# SOP-8_2_PCB.net
KiCad netlist of a schematic drawn in EAGLE
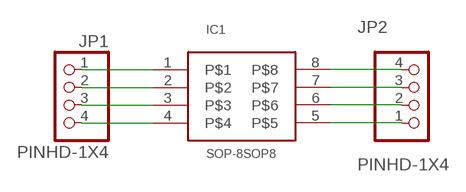
[diagram p0: schematic, sheet 1]

(export (version "E")
  (design (tool "Eeschema 10.0.6"))
  (components
    (comp (ref "IC1")
      (value "SOP-8SOP8")
      (footprint "eagle-import:SOP-8")
      (fields (field (name "MF") "Microchip") (field (name "MP") "AT24C02"))
      (libsource (lib "eagle-import") (part "SOP-8SOP8"))
    )
    (comp (ref "JP1")
      (value "PINHD-1X4")
      (footprint "eagle-import:1X04")
      (libsource (lib "eagle-import") (part "PINHD-1X4"))
    )
    (comp (ref "JP2")
      (value "PINHD-1X4")
      (footprint "eagle-import:1X04")
      (libsource (lib "eagle-import") (part "PINHD-1X4"))
    )
  )
  (nets
    (net (code "1") (name "Net-(IC1-P$1)") (class "Default")
      (node (ref "IC1") (pin "1") (pinfunction "P$1_1") (pintype "bidirectional"))
      (node (ref "JP1") (pin "1") (pinfunction "1_1") (pintype "passive"))
    )
    (net (code "2") (name "Net-(IC1-P$2)") (class "Default")
      (node (ref "IC1") (pin "2") (pinfunction "P$2_2") (pintype "bidirectional"))
      (node (ref "JP1") (pin "2") (pinfunction "2_2") (pintype "passive"))
    )
    (net (code "3") (name "Net-(IC1-P$3)") (class "Default")
      (node (ref "IC1") (pin "3") (pinfunction "P$3_3") (pintype "bidirectional"))
      (node (ref "JP1") (pin "3") (pinfunction "3_3") (pintype "passive"))
    )
    (net (code "4") (name "Net-(IC1-P$4)") (class "Default")
      (node (ref "IC1") (pin "4") (pinfunction "P$4_4") (pintype "bidirectional"))
      (node (ref "JP1") (pin "4") (pinfunction "4_4") (pintype "passive"))
    )
    (net (code "5") (name "Net-(IC1-P$5)") (class "Default")
      (node (ref "IC1") (pin "5") (pinfunction "P$5_5") (pintype "bidirectional"))
      (node (ref "JP2") (pin "1") (pinfunction "1_1") (pintype "passive"))
    )
    (net (code "6") (name "Net-(IC1-P$6)") (class "Default")
      (node (ref "IC1") (pin "6") (pinfunction "P$6_6") (pintype "bidirectional"))
      (node (ref "JP2") (pin "2") (pinfunction "2_2") (pintype "passive"))
    )
    (net (code "7") (name "Net-(IC1-P$7)") (class "Default")
      (node (ref "IC1") (pin "7") (pinfunction "P$7_7") (pintype "bidirectional"))
      (node (ref "JP2") (pin "3") (pinfunction "3_3") (pintype "passive"))
    )
    (net (code "8") (name "Net-(IC1-P$8)") (class "Default")
      (node (ref "IC1") (pin "8") (pinfunction "P$8_8") (pintype "bidirectional"))
      (node (ref "JP2") (pin "4") (pinfunction "4_4") (pintype "passive"))
    )
  )
)
